# AFE_DRL.net
KiCad netlist of a schematic drawn in Altium Designer
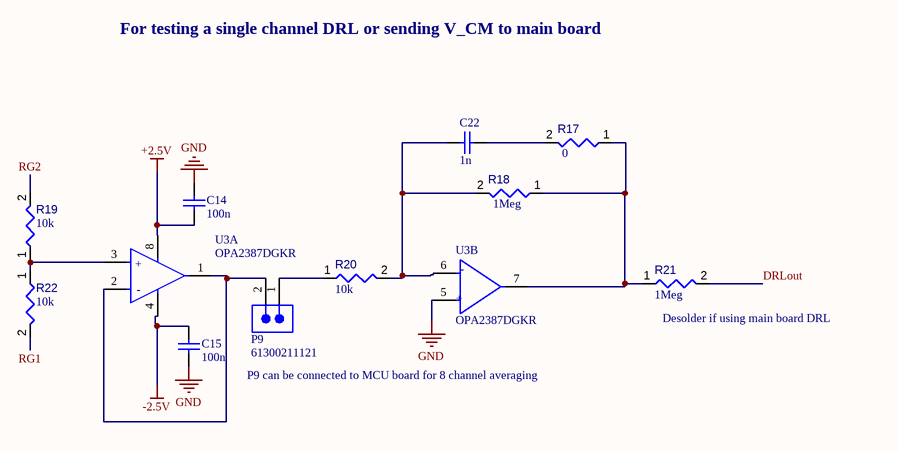
[diagram p0: AFE_DRL.SchDoc]

(export (version "E")
  (design (tool "Eeschema 10.0.6"))
  (components
    (comp (ref "C14")
      (value "100n")
      (footprint "WCAP-CSGP_0402_L1W0.5H0.5")
      (description "CAP CER 10000PF 50V X7R 0402")
      (fields (field (name "TOLERANCE") "10%"))
      (libsource (lib "Altium Content Vault") (part "Capacitor_Non-Polarized"))
    )
    (comp (ref "C15")
      (value "100n")
      (footprint "WCAP-CSGP_0402_L1W0.5H0.5")
      (description "CAP CER 10000PF 50V X7R 0402")
      (fields (field (name "TOLERANCE") "10%"))
      (libsource (lib "Altium Content Vault") (part "Capacitor_Non-Polarized"))
    )
    (comp (ref "C22")
      (value "1n")
      (footprint "WCAP-CSGP_0402_L1W0.5H0.5")
      (description "CAP CER 10000PF 50V X7R 0402")
      (fields (field (name "TOLERANCE") "10%"))
      (libsource (lib "Altium Content Vault") (part "Capacitor_Non-Polarized"))
    )
    (comp (ref "P9")
      (value "61300211121")
      (footprint "61300211121")
      (libsource (lib "Altium Content Vault") (part "Header_Male_1R_02P"))
    )
    (comp (ref "R17")
      (value "0")
      (footprint "RESC1005X40X25ML05T05")
      (description "Chip Resistor, 4.7 KOhm, +/- 1%, 63 mW, -55 to 155 degC, 0402 (1005 Metric)")
      (fields (field (name "TOLERANCE") "1%") (field (name "POWER") "63mW"))
      (libsource (lib "Christian Fenger") (part "RES-2"))
    )
    (comp (ref "R18")
      (value "1Meg")
      (footprint "RESC1005X40X25ML05T05")
      (description "Chip Resistor, 4.7 KOhm, +/- 1%, 63 mW, -55 to 155 degC, 0402 (1005 Metric)")
      (fields (field (name "TOLERANCE") "1%") (field (name "POWER") "63mW"))
      (libsource (lib "Christian Fenger") (part "RES-2"))
    )
    (comp (ref "R19")
      (value "10k")
      (footprint "RESC1005X40X25ML05T05")
      (description "Chip Resistor, 4.7 KOhm, +/- 1%, 63 mW, -55 to 155 degC, 0402 (1005 Metric)")
      (fields (field (name "TOLERANCE") "1%") (field (name "POWER") "63mW"))
      (libsource (lib "Christian Fenger") (part "RES-2"))
    )
    (comp (ref "R20")
      (value "10k")
      (footprint "RESC1005X40X25ML05T05")
      (description "Chip Resistor, 4.7 KOhm, +/- 1%, 63 mW, -55 to 155 degC, 0402 (1005 Metric)")
      (fields (field (name "TOLERANCE") "1%") (field (name "POWER") "63mW"))
      (libsource (lib "Christian Fenger") (part "RES-2"))
    )
    (comp (ref "R21")
      (value "1Meg")
      (footprint "RESC1005X40X25ML05T05")
      (description "Chip Resistor, 4.7 KOhm, +/- 1%, 63 mW, -55 to 155 degC, 0402 (1005 Metric)")
      (fields (field (name "TOLERANCE") "1%") (field (name "POWER") "63mW"))
      (libsource (lib "Christian Fenger") (part "RES-2"))
    )
    (comp (ref "R22")
      (value "10k")
      (footprint "RESC1005X40X25ML05T05")
      (description "Chip Resistor, 4.7 KOhm, +/- 1%, 63 mW, -55 to 155 degC, 0402 (1005 Metric)")
      (fields (field (name "TOLERANCE") "1%") (field (name "POWER") "63mW"))
      (libsource (lib "Christian Fenger") (part "RES-2"))
    )
    (comp (ref "U3")
      (value "OPA2387DGKR")
      (footprint "FP-DGK0008A-IPC_B")
      (description "ULTRA-HIGH PRECISION, ZERO-DRIFT")
      (libsource (lib "Altium Content Vault") (part "499df5fc91ff7ad023bcaf249d8becd"))
    )
  )
  (nets
    (net (code "1") (name "+2.5V") (class "Default")
      (node (ref "C14") (pin "1") (pinfunction "1_1") (pintype "passive"))
      (node (ref "U3") (pin "8") (pinfunction "V+_8") (pintype "power_in"))
    )
    (net (code "2") (name "-2.5V") (class "Default")
      (node (ref "C15") (pin "2") (pinfunction "2_2") (pintype "passive"))
      (node (ref "U3") (pin "4") (pinfunction "V-_4") (pintype "power_in"))
    )
    (net (code "3") (name "/DRLout") (class "Default")
      (node (ref "R21") (pin "2") (pinfunction "2_2") (pintype "passive"))
    )
    (net (code "4") (name "/RG1") (class "Default")
      (node (ref "R22") (pin "2") (pinfunction "2_2") (pintype "passive"))
    )
    (net (code "5") (name "/RG2") (class "Default")
      (node (ref "R19") (pin "2") (pinfunction "2_2") (pintype "passive"))
    )
    (net (code "6") (name "GND") (class "Default")
      (node (ref "C14") (pin "2") (pinfunction "2_2") (pintype "passive"))
      (node (ref "C15") (pin "1") (pinfunction "1_1") (pintype "passive"))
      (node (ref "U3") (pin "5") (pinfunction "+IN_B_5") (pintype "tri_state"))
    )
    (net (code "7") (name "Net-(C22-Pad1)") (class "Default")
      (node (ref "C22") (pin "1") (pinfunction "1_1") (pintype "passive"))
      (node (ref "R17") (pin "2") (pinfunction "2_2") (pintype "passive"))
    )
    (net (code "8") (name "Net-(P9-Pad1)") (class "Default")
      (node (ref "P9") (pin "1") (pinfunction "1_1") (pintype "passive"))
      (node (ref "R20") (pin "1") (pinfunction "1_1") (pintype "passive"))
    )
    (net (code "9") (name "Net-(U3A-+IN_A)") (class "Default")
      (node (ref "R19") (pin "1") (pinfunction "1_1") (pintype "passive"))
      (node (ref "R22") (pin "1") (pinfunction "1_1") (pintype "passive"))
      (node (ref "U3") (pin "3") (pinfunction "+IN_A_3") (pintype "tri_state"))
    )
    (net (code "10") (name "Net-(U3A--IN_A)") (class "Default")
      (node (ref "P9") (pin "2") (pinfunction "2_2") (pintype "passive"))
      (node (ref "U3") (pin "1") (pinfunction "OUT_A_1") (pintype "passive"))
      (node (ref "U3") (pin "2") (pinfunction "-IN_A_2") (pintype "tri_state"))
    )
    (net (code "11") (name "Net-(U3B--IN_B)") (class "Default")
      (node (ref "C22") (pin "2") (pinfunction "2_2") (pintype "passive"))
      (node (ref "R18") (pin "2") (pinfunction "2_2") (pintype "passive"))
      (node (ref "R20") (pin "2") (pinfunction "2_2") (pintype "passive"))
      (node (ref "U3") (pin "6") (pinfunction "-IN_B_6") (pintype "tri_state"))
    )
    (net (code "12") (name "Net-(U3B-OUT_B)") (class "Default")
      (node (ref "R17") (pin "1") (pinfunction "1_1") (pintype "passive"))
      (node (ref "R18") (pin "1") (pinfunction "1_1") (pintype "passive"))
      (node (ref "R21") (pin "1") (pinfunction "1_1") (pintype "passive"))
      (node (ref "U3") (pin "7") (pinfunction "OUT_B_7") (pintype "passive"))
    )
  )
)
